# Time_Reference_Generator.net
KiCad netlist of a schematic drawn in EAGLE
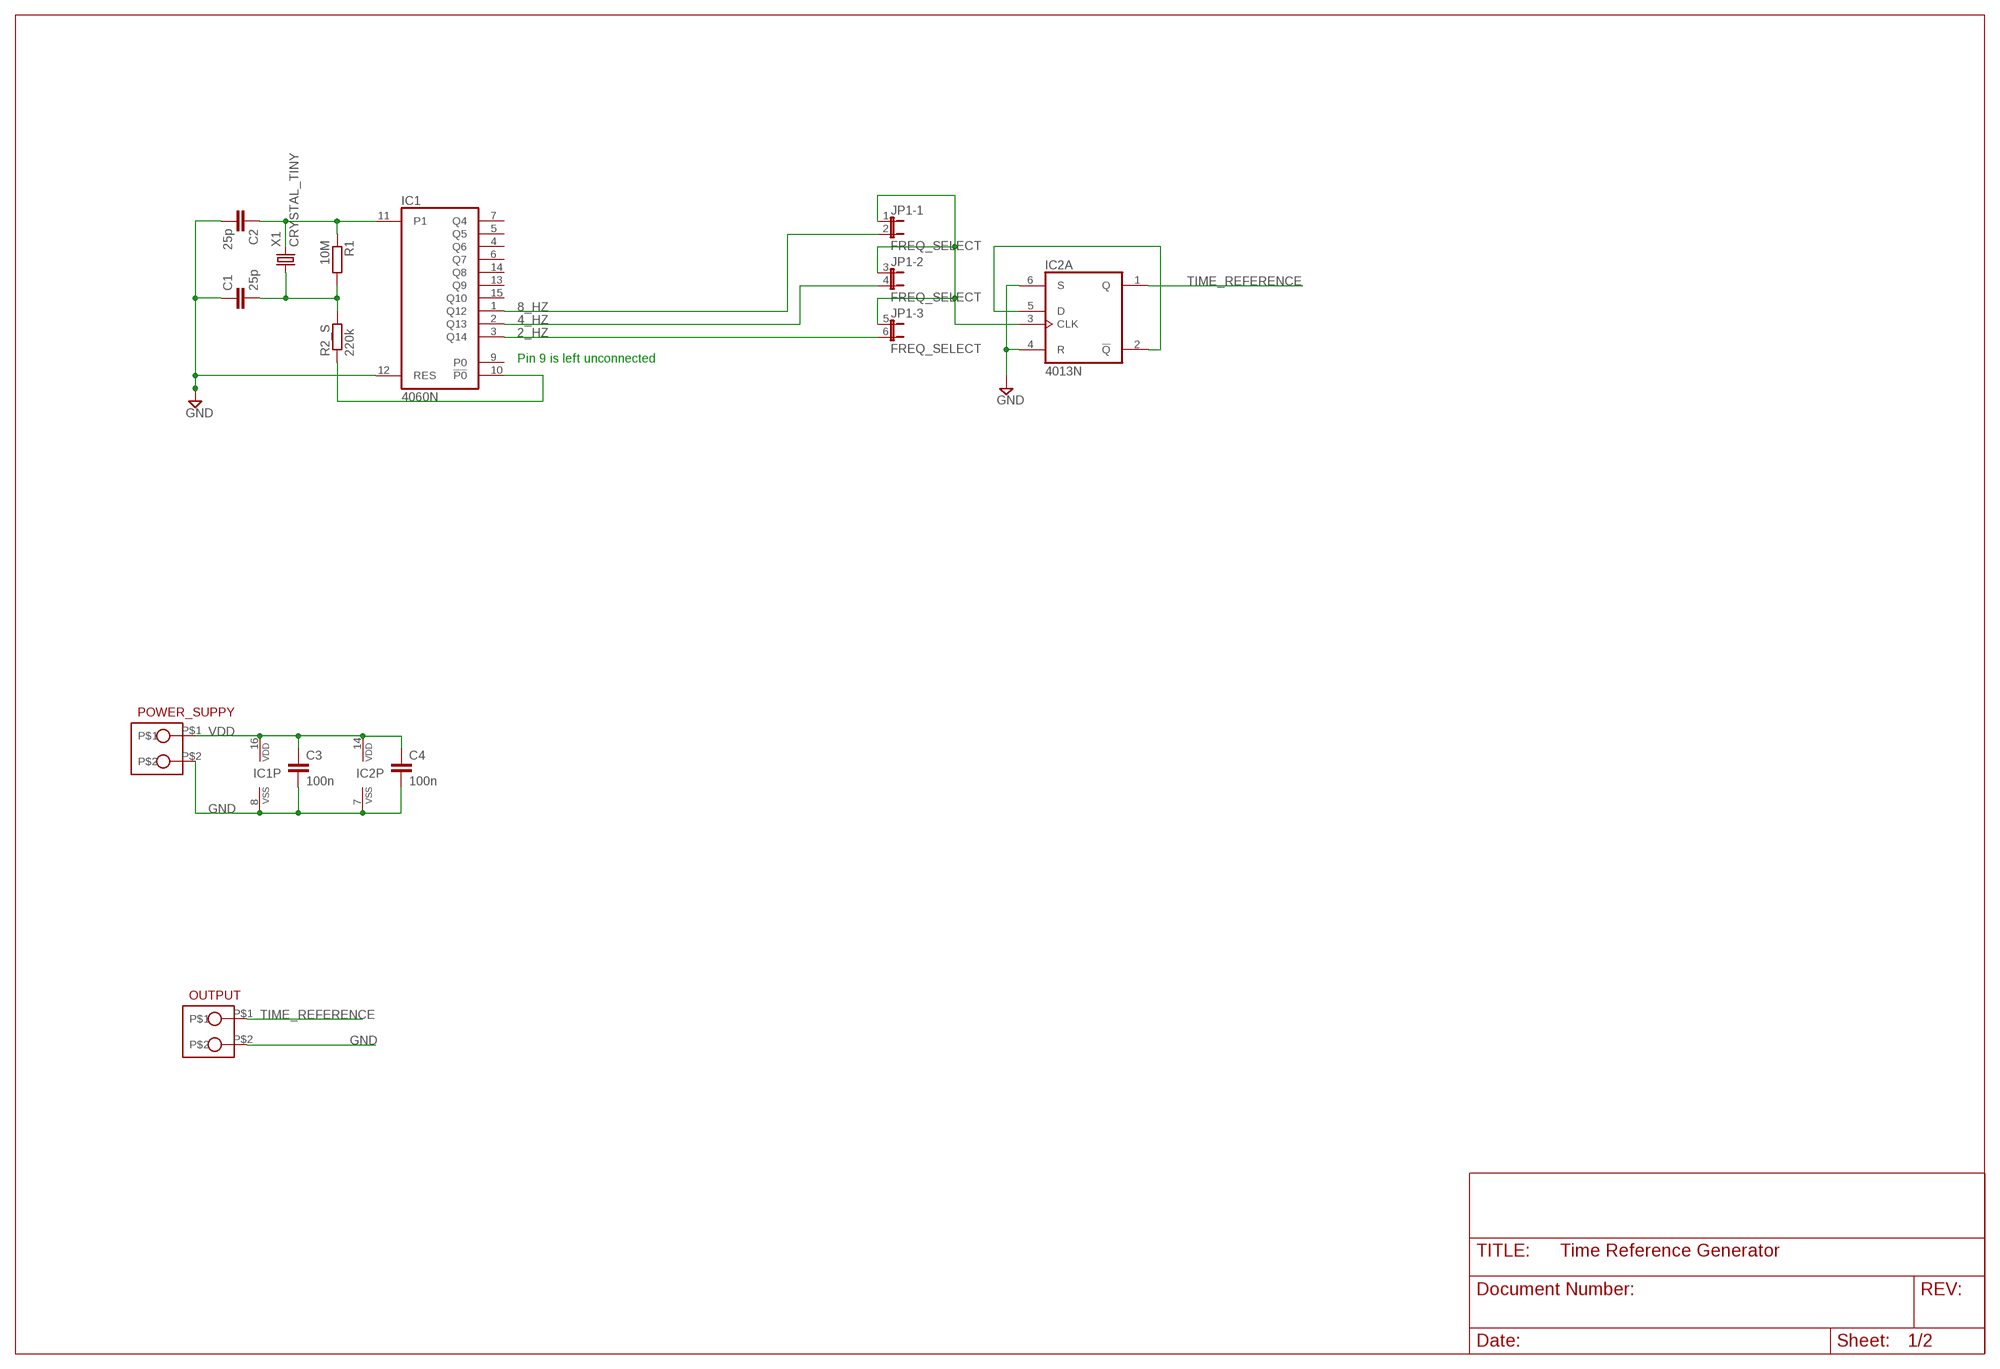
[diagram p0: schematic, sheet 1]

(export (version "E")
  (design (tool "Eeschema 10.0.6"))
  (components
    (comp (ref "C1")
      (value "25p")
      (footprint "eagle-import:C050-025X075")
      (libsource (lib "eagle-import") (part "C-EU050-025X075"))
    )
    (comp (ref "C2")
      (value "25p")
      (footprint "eagle-import:C050-025X075")
      (libsource (lib "eagle-import") (part "C-EU050-025X075"))
    )
    (comp (ref "C3")
      (value "100n")
      (footprint "eagle-import:C050-030X075")
      (libsource (lib "eagle-import") (part "C-EU050-030X075"))
    )
    (comp (ref "C4")
      (value "100n")
      (footprint "eagle-import:C050-030X075")
      (libsource (lib "eagle-import") (part "C-EU050-030X075"))
    )
    (comp (ref "IC1")
      (value "4060N")
      (footprint "eagle-import:DIL16")
      (libsource (lib "eagle-import") (part "4060N"))
    )
    (comp (ref "IC2")
      (value "4013N")
      (footprint "eagle-import:DIL14")
      (libsource (lib "eagle-import") (part "4013N"))
    )
    (comp (ref "JP1")
      (value "FREQ_SELECT")
      (footprint "eagle-import:JP3Q")
      (libsource (lib "eagle-import") (part "JP3QE"))
    )
    (comp (ref "OUTPUT")
      (value "CON_2_SIL")
      (footprint "eagle-import:SIL_2_0.2INCH")
      (libsource (lib "eagle-import") (part "CON_2_SIL"))
    )
    (comp (ref "POWER_SUPPY")
      (value "CON_2_SIL")
      (footprint "eagle-import:SIL_2_0.2INCH")
      (libsource (lib "eagle-import") (part "CON_2_SIL"))
    )
    (comp (ref "R1")
      (value "10M")
      (footprint "eagle-import:0207_10")
      (libsource (lib "eagle-import") (part "R-EU_0207/10"))
    )
    (comp (ref "R2_S")
      (value "220k")
      (footprint "eagle-import:0207_10")
      (libsource (lib "eagle-import") (part "R-EU_0207/10"))
    )
    (comp (ref "X1")
      (value "CRYSTAL_TINY")
      (footprint "eagle-import:WATCH-3X8-SPACED")
      (libsource (lib "eagle-import") (part "CRYSTAL_TINY"))
    )
  )
  (nets
    (net (code "1") (name "2_HZ") (class "Default")
      (node (ref "IC1") (pin "3") (pinfunction "Q14_3") (pintype "output"))
      (node (ref "JP1") (pin "6") (pinfunction "2_6") (pintype "passive"))
    )
    (net (code "2") (name "4_HZ") (class "Default")
      (node (ref "IC1") (pin "2") (pinfunction "Q13_2") (pintype "output"))
      (node (ref "JP1") (pin "4") (pinfunction "2_4") (pintype "passive"))
    )
    (net (code "3") (name "8_HZ") (class "Default")
      (node (ref "IC1") (pin "1") (pinfunction "Q12_1") (pintype "output"))
      (node (ref "JP1") (pin "2") (pinfunction "2_2") (pintype "passive"))
    )
    (net (code "4") (name "GND") (class "Default")
      (node (ref "C1") (pin "1") (pinfunction "1_1") (pintype "passive"))
      (node (ref "C2") (pin "2") (pinfunction "2_2") (pintype "passive"))
      (node (ref "C3") (pin "2") (pinfunction "2_2") (pintype "passive"))
      (node (ref "C4") (pin "2") (pinfunction "2_2") (pintype "passive"))
      (node (ref "IC1") (pin "12") (pinfunction "RES_12") (pintype "input"))
      (node (ref "IC1") (pin "8") (pinfunction "VSS_8") (pintype "power_in"))
      (node (ref "IC2") (pin "4") (pinfunction "R_4") (pintype "input"))
      (node (ref "IC2") (pin "6") (pinfunction "S_6") (pintype "input"))
      (node (ref "IC2") (pin "7") (pinfunction "VSS_7") (pintype "power_in"))
      (node (ref "OUTPUT") (pin "P$2") (pinfunction "P$2_P$2") (pintype "bidirectional"))
      (node (ref "POWER_SUPPY") (pin "P$2") (pinfunction "P$2_P$2") (pintype "bidirectional"))
    )
    (net (code "5") (name "Net-(C1-Pad2)") (class "Default")
      (node (ref "C1") (pin "2") (pinfunction "2_2") (pintype "passive"))
      (node (ref "R1") (pin "2") (pinfunction "2_2") (pintype "passive"))
      (node (ref "R2_S") (pin "2") (pinfunction "2_2") (pintype "passive"))
      (node (ref "X1") (pin "1") (pinfunction "1_1") (pintype "passive"))
    )
    (net (code "6") (name "Net-(IC1A-P1)") (class "Default")
      (node (ref "C2") (pin "1") (pinfunction "1_1") (pintype "passive"))
      (node (ref "IC1") (pin "11") (pinfunction "P1_11") (pintype "input"))
      (node (ref "R1") (pin "1") (pinfunction "1_1") (pintype "passive"))
      (node (ref "X1") (pin "2") (pinfunction "2_2") (pintype "passive"))
    )
    (net (code "7") (name "Net-(IC1A-~{P0})") (class "Default")
      (node (ref "IC1") (pin "10") (pinfunction "~{P0}_10") (pintype "output"))
      (node (ref "R2_S") (pin "1") (pinfunction "1_1") (pintype "passive"))
    )
    (net (code "8") (name "Net-(IC2A-CLK)") (class "Default")
      (node (ref "IC2") (pin "3") (pinfunction "CLK_3") (pintype "input"))
      (node (ref "JP1") (pin "1") (pinfunction "1_1") (pintype "passive"))
      (node (ref "JP1") (pin "3") (pinfunction "1_3") (pintype "passive"))
      (node (ref "JP1") (pin "5") (pinfunction "1_5") (pintype "passive"))
    )
    (net (code "9") (name "Net-(IC2A-D)") (class "Default")
      (node (ref "IC2") (pin "2") (pinfunction "~{Q}_2") (pintype "output"))
      (node (ref "IC2") (pin "5") (pinfunction "D_5") (pintype "input"))
    )
    (net (code "10") (name "TIME_REFERENCE") (class "Default")
      (node (ref "IC2") (pin "1") (pinfunction "Q_1") (pintype "output"))
      (node (ref "OUTPUT") (pin "P$1") (pinfunction "P$1_P$1") (pintype "bidirectional"))
    )
    (net (code "11") (name "VDD") (class "Default")
      (node (ref "C3") (pin "1") (pinfunction "1_1") (pintype "passive"))
      (node (ref "C4") (pin "1") (pinfunction "1_1") (pintype "passive"))
      (node (ref "IC1") (pin "16") (pinfunction "VDD_16") (pintype "power_in"))
      (node (ref "IC2") (pin "14") (pinfunction "VDD_14") (pintype "power_in"))
      (node (ref "POWER_SUPPY") (pin "P$1") (pinfunction "P$1_P$1") (pintype "bidirectional"))
    )
    (net (code "12") (name "unconnected-(IC1A-P0-Pad9)") (class "Default")
      (node (ref "IC1") (pin "9") (pinfunction "P0_9") (pintype "output"))
    )
    (net (code "13") (name "unconnected-(IC1A-Q4-Pad7)") (class "Default")
      (node (ref "IC1") (pin "7") (pinfunction "Q4_7") (pintype "output"))
    )
    (net (code "14") (name "unconnected-(IC1A-Q5-Pad5)") (class "Default")
      (node (ref "IC1") (pin "5") (pinfunction "Q5_5") (pintype "output"))
    )
    (net (code "15") (name "unconnected-(IC1A-Q6-Pad4)") (class "Default")
      (node (ref "IC1") (pin "4") (pinfunction "Q6_4") (pintype "output"))
    )
    (net (code "16") (name "unconnected-(IC1A-Q7-Pad6)") (class "Default")
      (node (ref "IC1") (pin "6") (pinfunction "Q7_6") (pintype "output"))
    )
    (net (code "17") (name "unconnected-(IC1A-Q8-Pad14)") (class "Default")
      (node (ref "IC1") (pin "14") (pinfunction "Q8_14") (pintype "output"))
    )
    (net (code "18") (name "unconnected-(IC1A-Q9-Pad13)") (class "Default")
      (node (ref "IC1") (pin "13") (pinfunction "Q9_13") (pintype "output"))
    )
    (net (code "19") (name "unconnected-(IC1A-Q10-Pad15)") (class "Default")
      (node (ref "IC1") (pin "15") (pinfunction "Q10_15") (pintype "output"))
    )
  )
)
